# MCU.net
KiCad netlist of a schematic drawn in Altium Designer
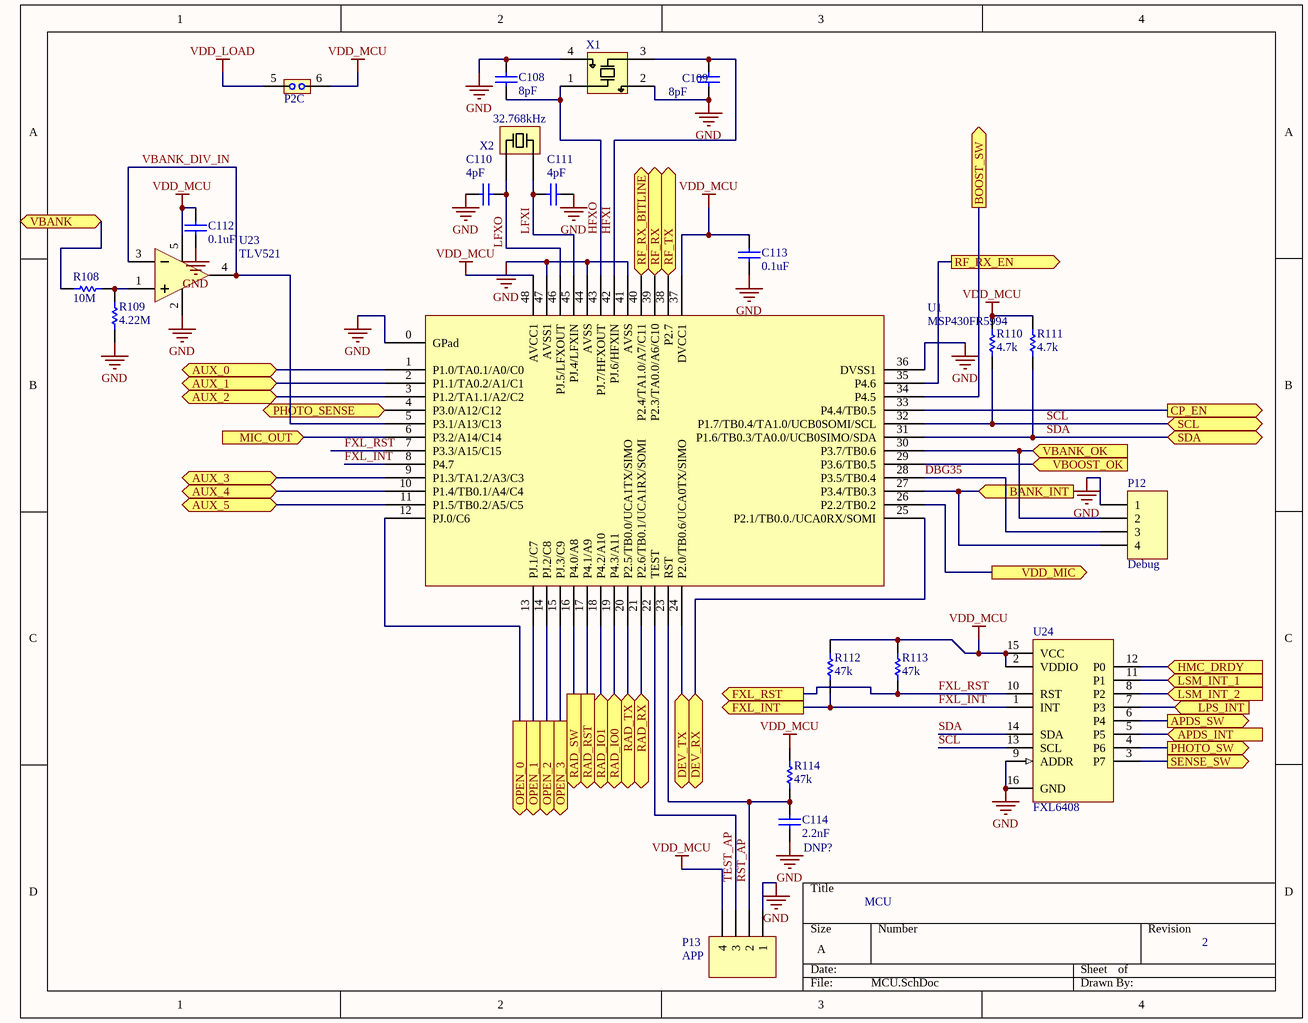
[diagram p0: MCU.SchDoc]

(export (version "E")
  (design (tool "Eeschema 10.0.6"))
  (components
    (comp (ref "C108")
      (value "8pF")
      (footprint "0402")
      (description "Ceramic Capacitor (Surface Mount)")
      (fields
        (field (name "MANUFACTURER") "Murata Electronics North America")
        (field (name "MANUFACTURER PART NUMBER") "GRM1555C1H8R0DA01D")
      )
      (libsource (lib "DRP_Basic_2014") (part "Cap"))
    )
    (comp (ref "C109")
      (value "8pF")
      (footprint "0402")
      (description "Ceramic Capacitor (Surface Mount)")
      (fields
        (field (name "MANUFACTURER") "Murata Electronics North America")
        (field (name "MANUFACTURER PART NUMBER") "GRM1555C1H8R0DA01D")
      )
      (libsource (lib "DRP_Basic_2014") (part "Cap"))
    )
    (comp (ref "C110")
      (value "4pF")
      (footprint "0402")
      (description "Ceramic Capacitor (Surface Mount)")
      (fields
        (field (name "MANUFACTURER") "Murata Electronics North America")
        (field (name "MANUFACTURER PART NUMBER") "GRM1555C1H4R0CA01D")
      )
      (libsource (lib "DRP_Basic_2014") (part "Cap"))
    )
    (comp (ref "C111")
      (value "4pF")
      (footprint "0402")
      (description "Ceramic Capacitor (Surface Mount)")
      (fields
        (field (name "MANUFACTURER") "Murata Electronics North America")
        (field (name "MANUFACTURER PART NUMBER") "GRM1555C1H4R0CA01D")
      )
      (libsource (lib "DRP_Basic_2014") (part "Cap"))
    )
    (comp (ref "C112")
      (value "0.1uF")
      (footprint "0603")
      (description "Ceramic Capacitor (Surface Mount)")
      (fields
        (field (name "MANUFACTURER") "Murata Electronics North America")
        (field (name "MANUFACTURER PART NUMBER") "GRM188R71C104KA01D")
      )
      (libsource (lib "DRP_Basic_2014") (part "Cap"))
    )
    (comp (ref "C113")
      (value "0.1uF")
      (footprint "0603")
      (description "Ceramic Capacitor (Surface Mount)")
      (fields
        (field (name "MANUFACTURER") "Murata Electronics North America")
        (field (name "MANUFACTURER PART NUMBER") "GRM188R71C104KA01D")
      )
      (libsource (lib "DRP_Basic_2014") (part "Cap"))
    )
    (comp (ref "C114")
      (value "2.2nF")
      (footprint "0603")
      (description "Ceramic Capacitor (Surface Mount)")
      (fields
        (field (name "MANUFACTURER") "Murata Electronics North America")
        (field (name "MANUFACTURER PART NUMBER") "GRM1885C1H222JA01D")
        (field (name "NOTE") "DNP?")
      )
      (libsource (lib "DRP_Basic_2014") (part "Cap"))
    )
    (comp (ref "P2") (value "JMPHDR_8") (footprint "MHDR2X8") (libsource (lib "Sprite") (part "JMPHDR_8")))
    (comp (ref "P12")
      (value "Debug")
      (footprint "MHDR1X4")
      (description "Header, 4-Pin")
      (fields
        (field (name "DIGI-KEY PART NUMBER") "952-3358-ND")
        (field (name "DISTRIBUTOR PART NUMBER") "855-M52-5000445")
        (field (name "PUBLISHER") "Altium Limited")
      )
      (libsource (lib "") (part "MHDR1X4_1"))
    )
    (comp (ref "P13")
      (value "APP")
      (footprint "MHDR1X4")
      (description "Header, 4-Pin")
      (fields
        (field (name "DISTRIBUTOR PART NUMBER") "855-M52-5000445")
        (field (name "MANUFACTURER") "Harwin Inc.")
        (field (name "PUBLISHER") "Altium Limited")
      )
      (libsource (lib "Miscellaneous Connectors") (part "MHDR1X4"))
    )
    (comp (ref "R108")
      (value "10M")
      (footprint "0603")
      (description "Chip Resistor (Surface Mount)")
      (fields
        (field (name "MANUFACTURER") "Yageo")
        (field (name "MANUFACTURER PART NUMBER") "RC0603JR-0710ML")
      )
      (libsource (lib "DRP_Basic_2014") (part "Res"))
    )
    (comp (ref "R109")
      (value "4.22M")
      (footprint "0603")
      (description "Chip Resistor (Surface Mount)")
      (fields
        (field (name "MANUFACTURER") "Vishay Dale")
        (field (name "MANUFACTURER PART NUMBER") "CRCW06034M22FKEA")
      )
      (libsource (lib "DRP_Basic_2014") (part "Res"))
    )
    (comp (ref "R110")
      (value "4.7k")
      (footprint "0603")
      (description "Chip Resistor (Surface Mount)")
      (fields
        (field (name "MANUFACTURER") "Yageo")
        (field (name "MANUFACTURER PART NUMBER") "RC0402JR-074K7L")
      )
      (libsource (lib "DRP_Basic_2014") (part "Res"))
    )
    (comp (ref "R111")
      (value "4.7k")
      (footprint "0603")
      (description "Chip Resistor (Surface Mount)")
      (fields
        (field (name "MANUFACTURER") "Yageo")
        (field (name "MANUFACTURER PART NUMBER") "RC0402JR-074K7L")
      )
      (libsource (lib "DRP_Basic_2014") (part "Res"))
    )
    (comp (ref "R112")
      (value "47k")
      (footprint "0603")
      (description "Chip Resistor (Surface Mount)")
      (fields
        (field (name "MANUFACTURER") "Yageo")
        (field (name "MANUFACTURER PART NUMBER") "RT0603DRD0747KL")
      )
      (libsource (lib "WISP_AD10") (part "Res"))
    )
    (comp (ref "R113")
      (value "47k")
      (footprint "0603")
      (description "Chip Resistor (Surface Mount)")
      (fields
        (field (name "MANUFACTURER") "Yageo")
        (field (name "MANUFACTURER PART NUMBER") "RT0603DRD0747KL")
      )
      (libsource (lib "WISP_AD10") (part "Res"))
    )
    (comp (ref "R114")
      (value "47k")
      (footprint "0603")
      (description "Chip Resistor (Surface Mount)")
      (fields
        (field (name "MANUFACTURER") "Yageo")
        (field (name "MANUFACTURER PART NUMBER") "RT0603DRD0747KL")
      )
      (libsource (lib "WISP_AD10") (part "Res"))
    )
    (comp (ref "U1")
      (value "MSP430FR5994")
      (footprint "48-QFN - Round Pin 1")
      (description "MSP430 - 48LQFP or 48QFN")
      (fields
        (field (name "DIGI-KEY PART NUMBER") "296-45416-1-ND")
        (field (name "MANUFACTURER") "Texas Instruments")
      )
      (libsource (lib "DRP_Basic_2014") (part "MSP430FR5994 48-pin"))
    )
    (comp (ref "U23")
      (value "TLV521")
      (footprint "SC70-5")
      (description "Low power opamp")
      (fields
        (field (name "DIGI-KEY PART NUMBER") "296-47441-1-ND")
        (field (name "DISTRIBUTOR PART NUMBER") "595-TLV521DCKR")
      )
      (libsource (lib "DRP_Basic_2014") (part "OPA333, 2333"))
    )
    (comp (ref "U24")
      (value "FXL6408")
      (footprint "16-UMLP")
      (fields
        (field (name "NAME") "FXL6408")
        (field (name "DIGI-KEY PART NUMBER") "FXL6408UMXCT-ND")
        (field (name "DISTRIBUTOR PART NUMBER") "512-FXL6408UMX")
        (field (name "MANUFACTURER") "ON Semiconductor / Fairchild")
      )
      (libsource (lib "Sprite") (part "FXL6408"))
    )
    (comp (ref "X1")
      (value "XTAL 4pin")
      (footprint "XTAL - 4Pin [2.5mm x 2.0mm]")
      (description "Crystal - 4-Pin Surface Mount")
      (fields
        (field (name "DIGI-KEY PART NUMBER") "XC1557CT-ND")
        (field (name "MANUFACTURER PART NUMBER") "ECS-240-8-36CKM-TR")
      )
      (libsource (lib "DRP_Basic_2014") (part "XTAL 4-pins"))
    )
    (comp (ref "X2")
      (value "32.768kHz")
      (footprint "XTAL - 2Pin [3.2mm x 1.5mm]")
      (description "Crystal - 2-Pin Surface Mount")
      (fields (field (name "DIGI-KEY PART NUMBER") "XC2162CT-ND") (field (name "MANUFACTURER") "ECS Inc."))
      (libsource (lib "DRP_Basic_2014") (part "XTAL 2-pins"))
    )
  )
  (nets
    (net (code "1") (name "/APDS_INT") (class "Default")
      (node (ref "U24") (pin "5") (pinfunction "P5_5") (pintype "passive"))
    )
    (net (code "2") (name "/APDS_SW") (class "Default")
      (node (ref "U24") (pin "6") (pinfunction "P4_6") (pintype "passive"))
    )
    (net (code "3") (name "/AUX_0") (class "Default")
      (node (ref "U1") (pin "1") (pinfunction "P1.0/TA0.1/A0/C0_1") (pintype "passive"))
    )
    (net (code "4") (name "/AUX_1") (class "Default")
      (node (ref "U1") (pin "2") (pinfunction "P1.1/TA0.2/A1/C1_2") (pintype "passive"))
    )
    (net (code "5") (name "/AUX_2") (class "Default")
      (node (ref "U1") (pin "3") (pinfunction "P1.2/TA1.1/A2/C2_3") (pintype "passive"))
    )
    (net (code "6") (name "/AUX_3") (class "Default")
      (node (ref "U1") (pin "9") (pinfunction "P1.3/TA1.2/A3/C3_9") (pintype "passive"))
    )
    (net (code "7") (name "/AUX_4") (class "Default")
      (node (ref "U1") (pin "10") (pinfunction "P1.4/TB0.1/A4/C4_10") (pintype "passive"))
    )
    (net (code "8") (name "/AUX_5") (class "Default")
      (node (ref "U1") (pin "11") (pinfunction "P1.5/TB0.2/A5/C5_11") (pintype "passive"))
    )
    (net (code "9") (name "/BANK_INT") (class "Default")
      (node (ref "P12") (pin "4") (pinfunction "4_4") (pintype "passive"))
      (node (ref "U1") (pin "27") (pinfunction "P3.4/TB0.3_27") (pintype "passive"))
    )
    (net (code "10") (name "/BOOST_SW") (class "Default")
      (node (ref "U1") (pin "34") (pinfunction "P4.5_34") (pintype "passive"))
    )
    (net (code "11") (name "/CP_EN") (class "Default")
      (node (ref "U1") (pin "33") (pinfunction "P4.4/TB0.5_33") (pintype "passive"))
    )
    (net (code "12") (name "/DBG35") (class "Default")
      (node (ref "P12") (pin "3") (pinfunction "3_3") (pintype "passive"))
      (node (ref "U1") (pin "28") (pinfunction "P3.5/TB0.4_28") (pintype "passive"))
    )
    (net (code "13") (name "/DEV_RX") (class "Default")
      (node (ref "U1") (pin "25") (pinfunction "P2.1/TB0.0./UCA0RX/SOMI_25") (pintype "passive"))
    )
    (net (code "14") (name "/DEV_TX") (class "Default")
      (node (ref "U1") (pin "24") (pinfunction "P2.0/TB0.6/UCA0TX/SIMO_24") (pintype "passive"))
    )
    (net (code "15") (name "/FXL_INT") (class "Default")
      (node (ref "R112") (pin "1") (pinfunction "1_1") (pintype "passive"))
      (node (ref "U1") (pin "8") (pinfunction "P4.7_8") (pintype "passive"))
      (node (ref "U24") (pin "1") (pinfunction "INT_1") (pintype "open_collector"))
    )
    (net (code "16") (name "/FXL_RST") (class "Default")
      (node (ref "R113") (pin "1") (pinfunction "1_1") (pintype "passive"))
      (node (ref "U1") (pin "7") (pinfunction "P3.3/A15/C15_7") (pintype "passive"))
      (node (ref "U24") (pin "10") (pinfunction "RST_10") (pintype "open_collector"))
    )
    (net (code "17") (name "/HFXI") (class "Default")
      (node (ref "C109") (pin "2") (pinfunction "2_2") (pintype "passive"))
      (node (ref "U1") (pin "42") (pinfunction "PJ.6/HFXIN_42") (pintype "passive"))
      (node (ref "X1") (pin "3") (pinfunction "XOUT_3") (pintype "passive"))
    )
    (net (code "18") (name "/HFXO") (class "Default")
      (node (ref "C108") (pin "1") (pinfunction "1_1") (pintype "passive"))
      (node (ref "U1") (pin "43") (pinfunction "PJ.7/HFXOUT_43") (pintype "passive"))
      (node (ref "X1") (pin "1") (pinfunction "XIN_1") (pintype "passive"))
    )
    (net (code "19") (name "/HMC_DRDY") (class "Default")
      (node (ref "U24") (pin "12") (pinfunction "P0_12") (pintype "passive"))
    )
    (net (code "20") (name "/LFXI") (class "Default")
      (node (ref "C111") (pin "1") (pinfunction "1_1") (pintype "passive"))
      (node (ref "U1") (pin "45") (pinfunction "PJ.4/LFXIN_45") (pintype "passive"))
      (node (ref "X2") (pin "1") (pinfunction "1_1") (pintype "power_in"))
    )
    (net (code "21") (name "/LFXO") (class "Default")
      (node (ref "C110") (pin "2") (pinfunction "2_2") (pintype "passive"))
      (node (ref "U1") (pin "46") (pinfunction "PJ.5/LFXOUT_46") (pintype "passive"))
      (node (ref "X2") (pin "2") (pinfunction "2_2") (pintype "power_in"))
    )
    (net (code "22") (name "/LPS_INT") (class "Default")
      (node (ref "U24") (pin "7") (pinfunction "P3_7") (pintype "passive"))
    )
    (net (code "23") (name "/LSM_INT_1") (class "Default")
      (node (ref "U24") (pin "11") (pinfunction "P1_11") (pintype "passive"))
    )
    (net (code "24") (name "/LSM_INT_2") (class "Default")
      (node (ref "U24") (pin "8") (pinfunction "P2_8") (pintype "passive"))
    )
    (net (code "25") (name "/MIC_OUT") (class "Default")
      (node (ref "U1") (pin "6") (pinfunction "P3.2/A14/C14_6") (pintype "passive"))
    )
    (net (code "26") (name "/OPEN_0") (class "Default")
      (node (ref "U1") (pin "12") (pinfunction "PJ.0/C6_12") (pintype "passive"))
    )
    (net (code "27") (name "/OPEN_1") (class "Default")
      (node (ref "U1") (pin "13") (pinfunction "PJ.1/C7_13") (pintype "passive"))
    )
    (net (code "28") (name "/OPEN_2") (class "Default")
      (node (ref "U1") (pin "14") (pinfunction "PJ.2/C8_14") (pintype "passive"))
    )
    (net (code "29") (name "/OPEN_3") (class "Default")
      (node (ref "U1") (pin "15") (pinfunction "PJ.3/C9_15") (pintype "passive"))
    )
    (net (code "30") (name "/PHOTO_SENSE") (class "Default")
      (node (ref "U1") (pin "4") (pinfunction "P3.0/A12/C12_4") (pintype "passive"))
    )
    (net (code "31") (name "/PHOTO_SW") (class "Default")
      (node (ref "U24") (pin "4") (pinfunction "P6_4") (pintype "passive"))
    )
    (net (code "32") (name "/RAD_IO0") (class "Default")
      (node (ref "U1") (pin "19") (pinfunction "P4.3/A11_19") (pintype "passive"))
    )
    (net (code "33") (name "/RAD_IO1") (class "Default")
      (node (ref "U1") (pin "18") (pinfunction "P4.2/A10_18") (pintype "passive"))
    )
    (net (code "34") (name "/RAD_RST") (class "Default")
      (node (ref "U1") (pin "17") (pinfunction "P4.1/A9_17") (pintype "passive"))
    )
    (net (code "35") (name "/RAD_RX") (class "Default")
      (node (ref "U1") (pin "21") (pinfunction "P2.6/TB0.1/UCA1RX/SOMI_21") (pintype "passive"))
    )
    (net (code "36") (name "/RAD_SW") (class "Default")
      (node (ref "U1") (pin "16") (pinfunction "P4.0/A8_16") (pintype "passive"))
    )
    (net (code "37") (name "/RAD_TX") (class "Default")
      (node (ref "U1") (pin "20") (pinfunction "P2.5/TB0.0/UCA1TX/SIMO_20") (pintype "passive"))
    )
    (net (code "38") (name "/RF_RX") (class "Default")
      (node (ref "U1") (pin "39") (pinfunction "P2.3/TA0.0/A6/C10_39") (pintype "passive"))
    )
    (net (code "39") (name "/RF_RX_BITLINE") (class "Default")
      (node (ref "U1") (pin "40") (pinfunction "P2.4/TA1.0/A7/C11_40") (pintype "passive"))
    )
    (net (code "40") (name "/RF_RX_EN") (class "Default")
      (node (ref "U1") (pin "35") (pinfunction "P4.6_35") (pintype "passive"))
    )
    (net (code "41") (name "/RF_TX") (class "Default")
      (node (ref "U1") (pin "38") (pinfunction "P2.7_38") (pintype "passive"))
    )
    (net (code "42") (name "/RST_AP") (class "Default")
      (node (ref "C114") (pin "1") (pinfunction "1_1") (pintype "passive"))
      (node (ref "P13") (pin "2") (pinfunction "2_2") (pintype "passive"))
      (node (ref "R114") (pin "1") (pinfunction "1_1") (pintype "passive"))
      (node (ref "U1") (pin "23") (pinfunction "RST_23") (pintype "passive"))
    )
    (net (code "43") (name "/SCL") (class "Default")
      (node (ref "R110") (pin "1") (pinfunction "1_1") (pintype "passive"))
      (node (ref "U1") (pin "32") (pinfunction "P1.7/TB0.4/TA1.0/UCB0SOMI/SCL_32") (pintype "passive"))
      (node (ref "U24") (pin "13") (pinfunction "SCL_13") (pintype "open_collector"))
    )
    (net (code "44") (name "/SDA") (class "Default")
      (node (ref "R111") (pin "1") (pinfunction "1_1") (pintype "passive"))
      (node (ref "U1") (pin "31") (pinfunction "P1.6/TB0.3/TA0.0/UCB0SIMO/SDA_31") (pintype "passive"))
      (node (ref "U24") (pin "14") (pinfunction "SDA_14") (pintype "open_collector"))
    )
    (net (code "45") (name "/SENSE_SW") (class "Default")
      (node (ref "U24") (pin "3") (pinfunction "P7_3") (pintype "passive"))
    )
    (net (code "46") (name "/TEST_AP") (class "Default")
      (node (ref "P13") (pin "3") (pinfunction "3_3") (pintype "passive"))
      (node (ref "U1") (pin "22") (pinfunction "TEST_22") (pintype "passive"))
    )
    (net (code "47") (name "/VBANK") (class "Default")
      (node (ref "R108") (pin "1") (pinfunction "1_1") (pintype "passive"))
    )
    (net (code "48") (name "/VBANK_DIV_IN") (class "Default")
      (node (ref "U1") (pin "5") (pinfunction "P3.1/A13/C13_5") (pintype "passive"))
      (node (ref "U23") (pin "3") (pinfunction "IN+_3") (pintype "passive"))
      (node (ref "U23") (pin "4") (pinfunction "TAB_4") (pintype "passive"))
    )
    (net (code "49") (name "/VBANK_OK") (class "Default")
      (node (ref "P12") (pin "2") (pinfunction "2_2") (pintype "passive"))
      (node (ref "U1") (pin "30") (pinfunction "P3.7/TB0.6_30") (pintype "passive"))
    )
    (net (code "50") (name "/VBOOST_OK") (class "Default")
      (node (ref "U1") (pin "29") (pinfunction "P3.6/TB0.5_29") (pintype "passive"))
    )
    (net (code "51") (name "/VDD_MIC") (class "Default")
      (node (ref "U1") (pin "26") (pinfunction "P2.2/TB0.2_26") (pintype "passive"))
    )
    (net (code "52") (name "GND") (class "Default")
      (node (ref "C108") (pin "2") (pinfunction "2_2") (pintype "passive"))
      (node (ref "C109") (pin "1") (pinfunction "1_1") (pintype "passive"))
      (node (ref "C110") (pin "1") (pinfunction "1_1") (pintype "passive"))
      (node (ref "C111") (pin "2") (pinfunction "2_2") (pintype "passive"))
      (node (ref "C112") (pin "2") (pinfunction "2_2") (pintype "passive"))
      (node (ref "C113") (pin "2") (pinfunction "2_2") (pintype "passive"))
      (node (ref "C114") (pin "2") (pinfunction "2_2") (pintype "passive"))
      (node (ref "P12") (pin "1") (pinfunction "1_1") (pintype "passive"))
      (node (ref "P13") (pin "1") (pinfunction "1_1") (pintype "passive"))
      (node (ref "R109") (pin "2") (pinfunction "2_2") (pintype "passive"))
      (node (ref "U1") (pin "0") (pinfunction "GPad_0") (pintype "power_in"))
      (node (ref "U1") (pin "36") (pinfunction "DVSS1_36") (pintype "power_in"))
      (node (ref "U1") (pin "41") (pinfunction "AVSS_41") (pintype "power_in"))
      (node (ref "U1") (pin "44") (pinfunction "AVSS_44") (pintype "power_in"))
      (node (ref "U1") (pin "47") (pinfunction "AVSS1_47") (pintype "power_in"))
      (node (ref "U23") (pin "2") (pinfunction "IN-_2") (pintype "passive"))
      (node (ref "U24") (pin "16") (pinfunction "GND_16") (pintype "power_in"))
      (node (ref "U24") (pin "9") (pinfunction "ADDR_9") (pintype "input"))
      (node (ref "X1") (pin "2") (pinfunction "Gnd_2") (pintype "passive"))
      (node (ref "X1") (pin "4") (pinfunction "Gnd_4") (pintype "passive"))
    )
    (net (code "53") (name "Net-(R108-Pad2)") (class "Default")
      (node (ref "R108") (pin "2") (pinfunction "2_2") (pintype "passive"))
      (node (ref "R109") (pin "1") (pinfunction "1_1") (pintype "passive"))
      (node (ref "U23") (pin "1") (pinfunction "OS_NUL_1") (pintype "passive"))
    )
    (net (code "54") (name "VDD_LOAD") (class "Default")
      (node (ref "P2") (pin "5") (pinfunction "5_5") (pintype "passive"))
    )
    (net (code "55") (name "VDD_MCU") (class "Default")
      (node (ref "C112") (pin "1") (pinfunction "1_1") (pintype "passive"))
      (node (ref "C113") (pin "1") (pinfunction "1_1") (pintype "passive"))
      (node (ref "P13") (pin "4") (pinfunction "4_4") (pintype "passive"))
      (node (ref "P2") (pin "6") (pinfunction "6_6") (pintype "passive"))
      (node (ref "R110") (pin "2") (pinfunction "2_2") (pintype "passive"))
      (node (ref "R111") (pin "2") (pinfunction "2_2") (pintype "passive"))
      (node (ref "R112") (pin "2") (pinfunction "2_2") (pintype "passive"))
      (node (ref "R113") (pin "2") (pinfunction "2_2") (pintype "passive"))
      (node (ref "R114") (pin "2") (pinfunction "2_2") (pintype "passive"))
      (node (ref "U1") (pin "37") (pinfunction "DVCC1_37") (pintype "power_in"))
      (node (ref "U1") (pin "48") (pinfunction "AVCC1_48") (pintype "power_in"))
      (node (ref "U23") (pin "5") (pinfunction "OS_NUL_5") (pintype "passive"))
      (node (ref "U24") (pin "15") (pinfunction "VCC_15") (pintype "power_in"))
      (node (ref "U24") (pin "2") (pinfunction "VDDIO_2") (pintype "power_in"))
    )
  )
)
